# rapidshark-clip-detector-mk-1_0.net
KiCad netlist of a schematic drawn in EAGLE
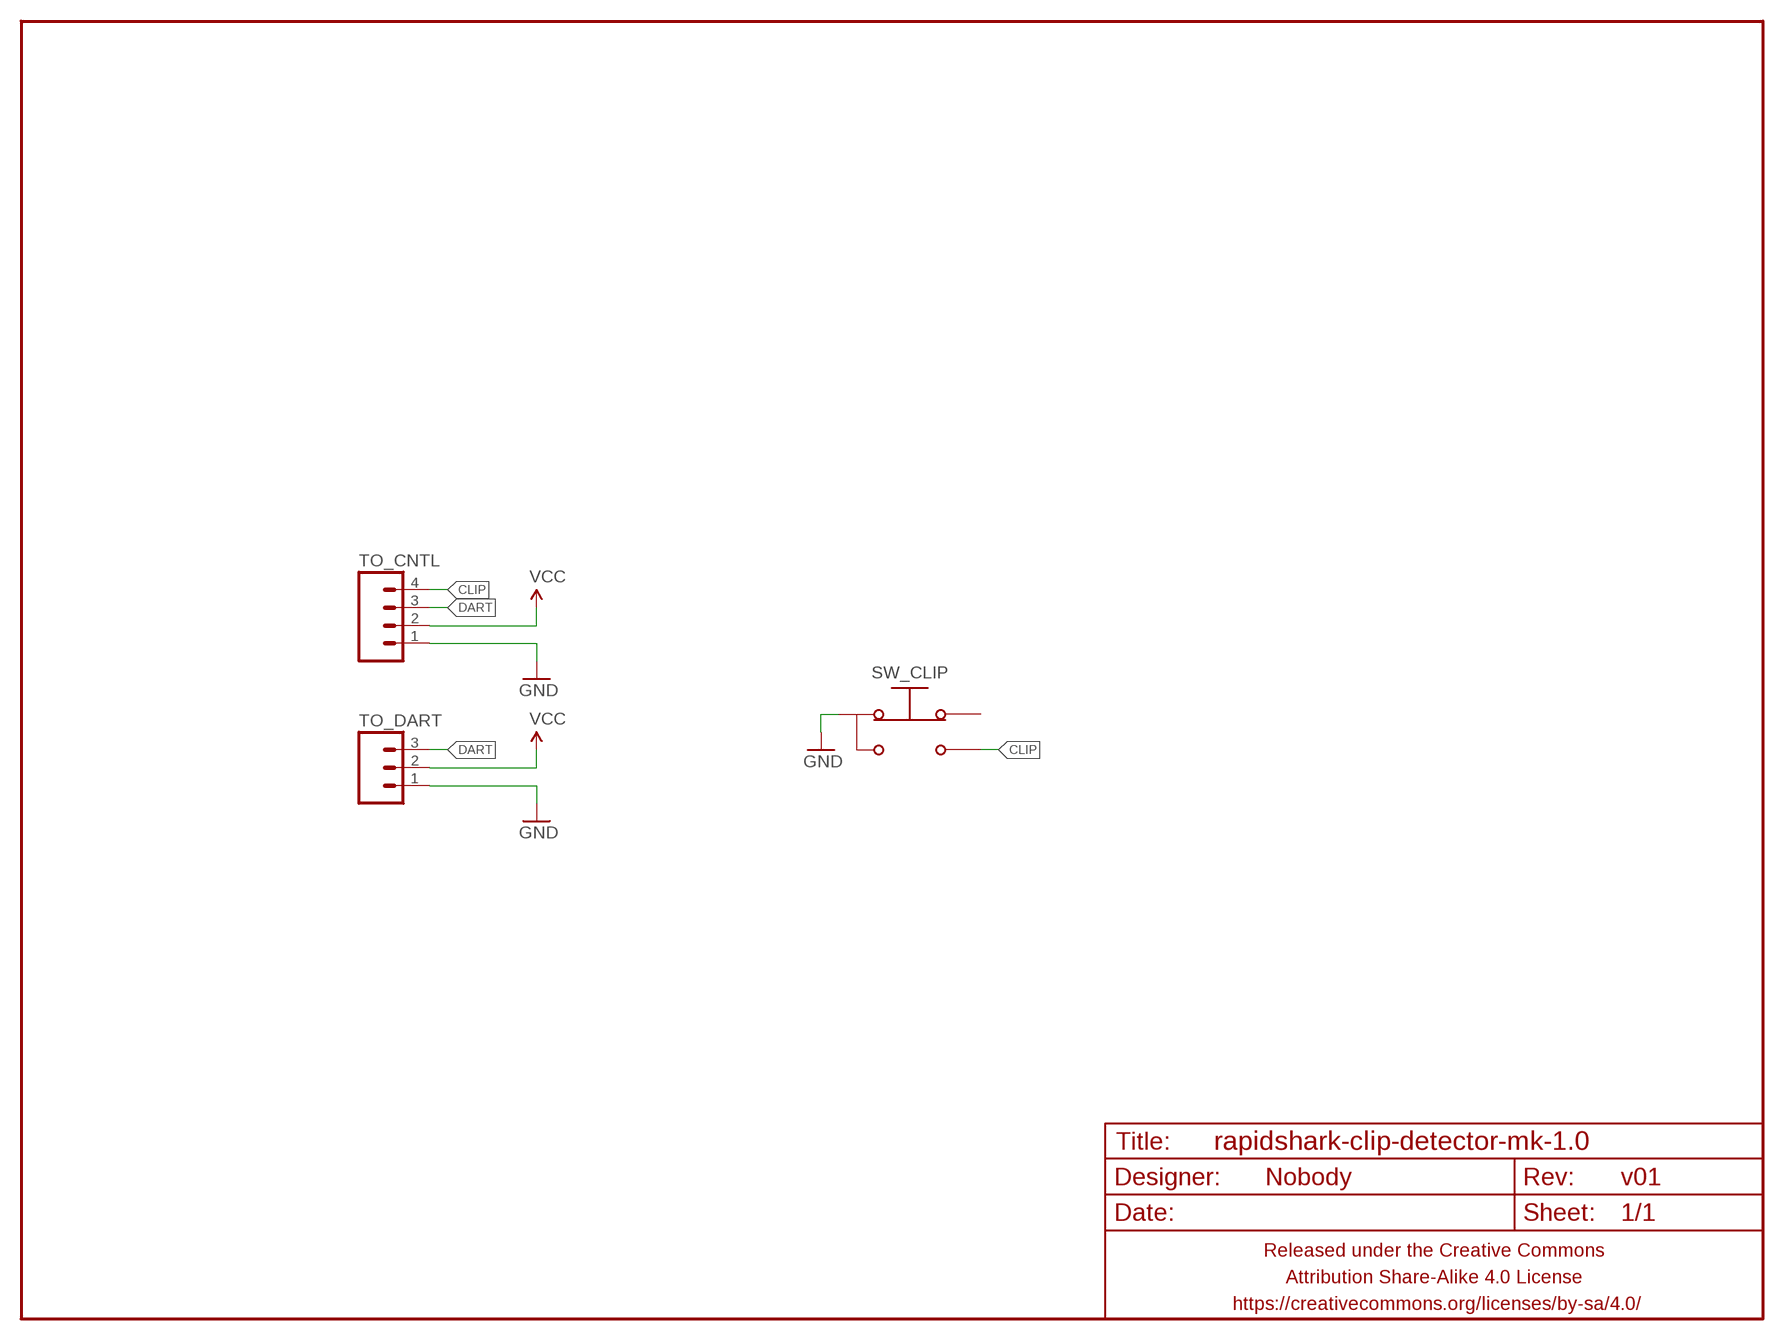
[diagram p0: schematic, sheet 1]

(export (version "E")
  (design (tool "Eeschema 10.0.6"))
  (components
    (comp (ref "FRAME1")
      (value "FRAME-LETTERNO_PACKAGE")
      (footprint "eagle-import:DUMMY")
      (fields (field (name "DESIGNER") "Nobody"))
      (libsource (lib "eagle-import") (part "FRAME-LETTERNO_PACKAGE"))
    )
    (comp (ref "SW_CLIP")
      (value "SPDT-NO-TACTPTH-RA-DETECT-3MM")
      (footprint "eagle-import:SWITCH-DETECH-SPDT-3MM")
      (libsource (lib "eagle-import") (part "SPDT-NO-TACTPTH-RA-DETECT-3MM"))
    )
    (comp (ref "TO_CNTL")
      (value "M04JST-PTH-VERT")
      (footprint "eagle-import:JST-4-PH-VERT-PTH")
      (libsource (lib "eagle-import") (part "M04JST-PTH-VERT"))
    )
    (comp (ref "TO_DART")
      (value "M03JST-PTH-VERT")
      (footprint "eagle-import:JST-3-PH-VERT-PTH")
      (libsource (lib "eagle-import") (part "M03JST-PTH-VERT"))
    )
  )
  (nets
    (net (code "1") (name "CLIP") (class "Default")
      (node (ref "SW_CLIP") (pin "3") (pinfunction "NO_3") (pintype "bidirectional"))
      (node (ref "TO_CNTL") (pin "4") (pinfunction "4_4") (pintype "passive"))
    )
    (net (code "2") (name "DART") (class "Default")
      (node (ref "TO_CNTL") (pin "3") (pinfunction "3_3") (pintype "passive"))
      (node (ref "TO_DART") (pin "3") (pinfunction "3_3") (pintype "passive"))
    )
    (net (code "3") (name "GND") (class "Default")
      (node (ref "SW_CLIP") (pin "2") (pinfunction "COM_2") (pintype "bidirectional"))
      (node (ref "TO_CNTL") (pin "1") (pinfunction "1_1") (pintype "passive"))
      (node (ref "TO_DART") (pin "1") (pinfunction "1_1") (pintype "passive"))
    )
    (net (code "4") (name "VCC") (class "Default")
      (node (ref "TO_CNTL") (pin "2") (pinfunction "2_2") (pintype "passive"))
      (node (ref "TO_DART") (pin "2") (pinfunction "2_2") (pintype "passive"))
    )
    (net (code "5") (name "unconnected-(SW_CLIP-NC-Pad1)") (class "Default")
      (node (ref "SW_CLIP") (pin "1") (pinfunction "NC_1") (pintype "bidirectional"))
    )
  )
)
